# cell.net
KiCad netlist of a schematic drawn in EAGLE
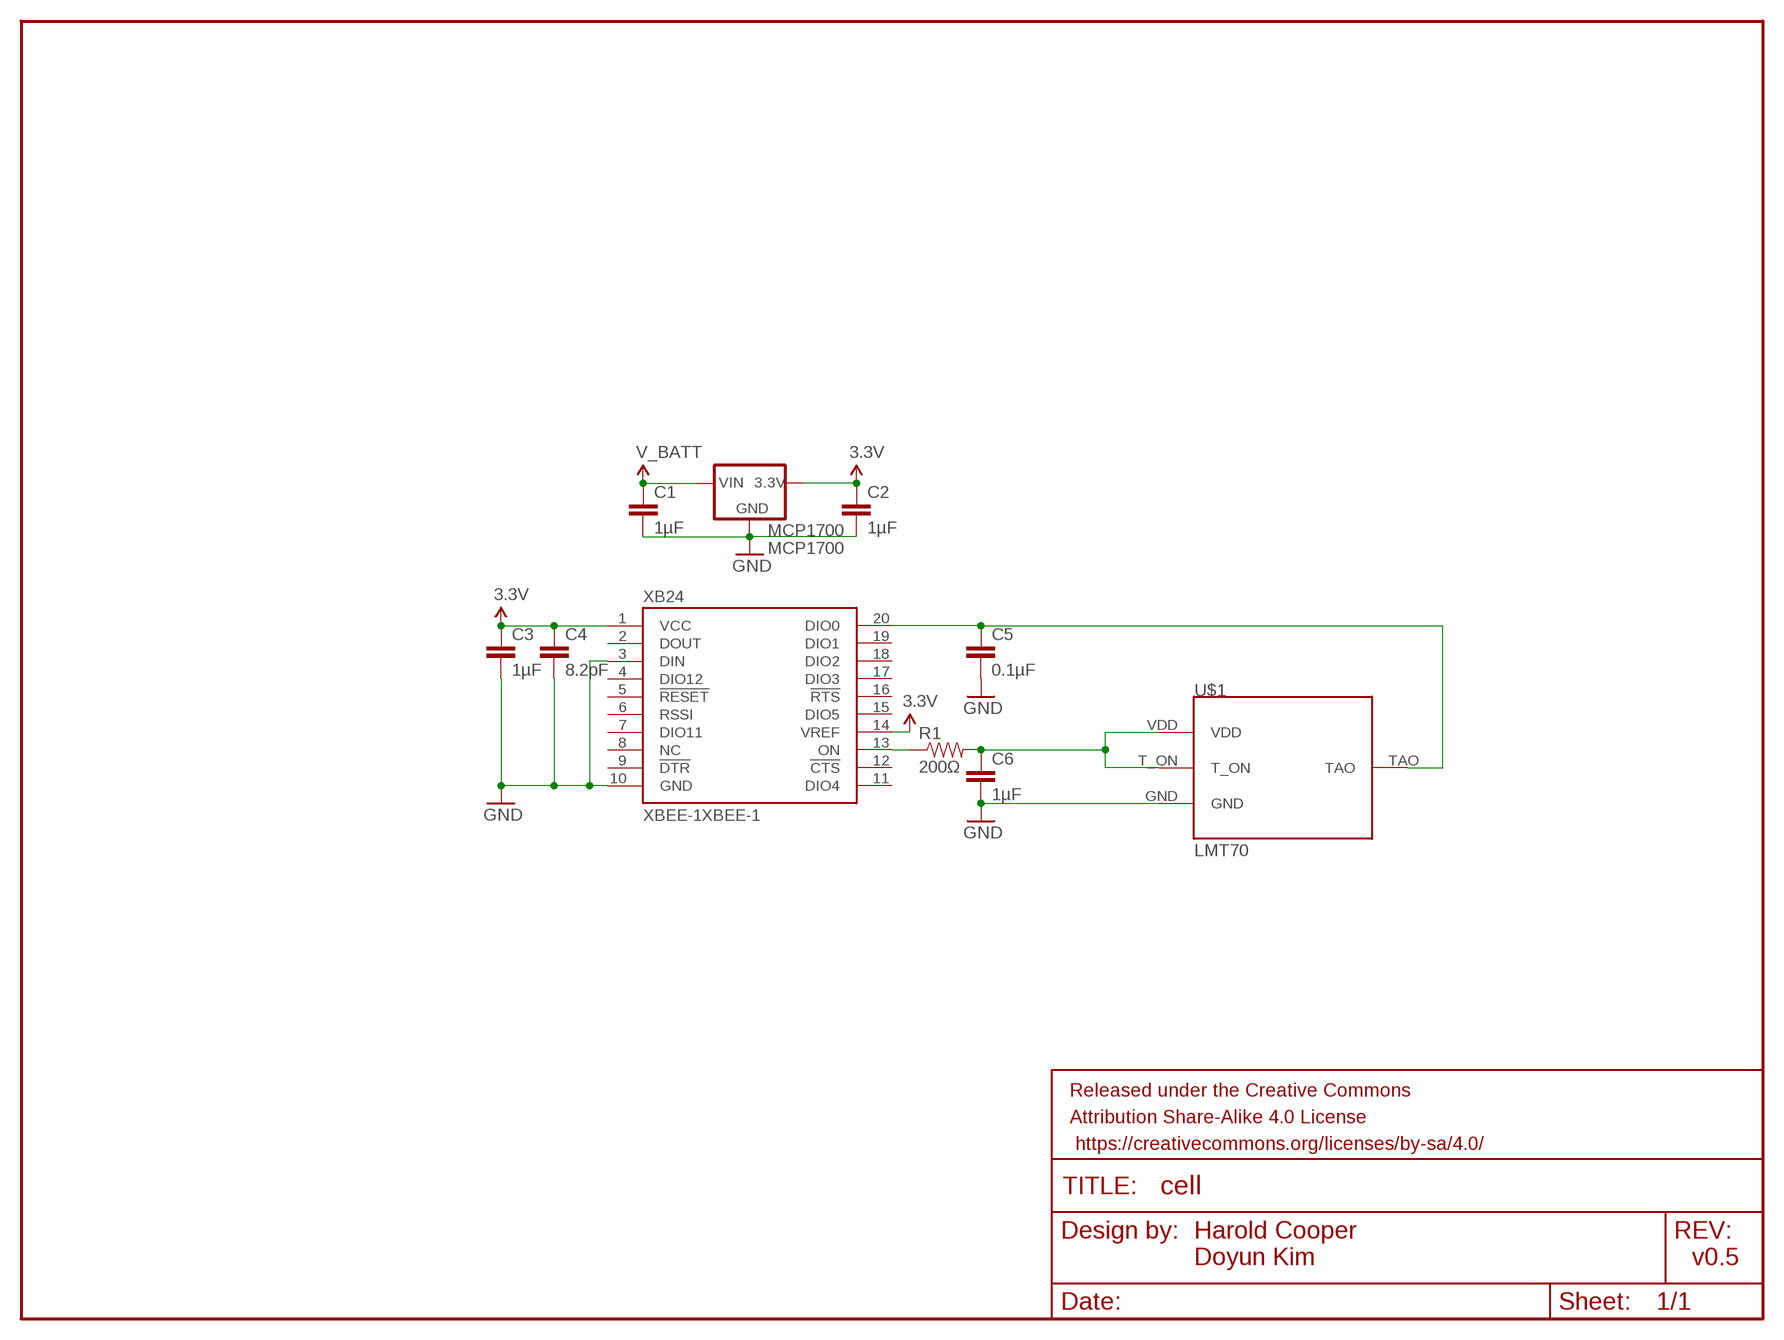
[diagram p0: schematic, sheet 1]

(export (version "E")
  (design (tool "Eeschema 10.0.6"))
  (components
    (comp (ref "C1")
      (value "1µF")
      (footprint "eagle-import:0805")
      (libsource (lib "eagle-import") (part "CAP0805"))
    )
    (comp (ref "C2")
      (value "1µF")
      (footprint "eagle-import:0805")
      (libsource (lib "eagle-import") (part "CAP0805"))
    )
    (comp (ref "C3")
      (value "1µF")
      (footprint "eagle-import:0805")
      (libsource (lib "eagle-import") (part "CAP0805"))
    )
    (comp (ref "C4")
      (value "8.2pF")
      (footprint "eagle-import:0805")
      (libsource (lib "eagle-import") (part "CAP0805"))
    )
    (comp (ref "C5")
      (value "0.1µF")
      (footprint "eagle-import:0805")
      (libsource (lib "eagle-import") (part "CAP0805"))
    )
    (comp (ref "C6")
      (value "1µF")
      (footprint "eagle-import:0805")
      (libsource (lib "eagle-import") (part "CAP0805"))
    )
    (comp (ref "FRAME1")
      (value "FRAME-LETTER")
      (footprint "eagle-import:CREATIVE_COMMONS")
      (libsource (lib "eagle-import") (part "FRAME-LETTER"))
    )
    (comp (ref "MCP1700")
      (value "MCP1700")
      (footprint "eagle-import:SOT-89-3")
      (libsource (lib "eagle-import") (part "MCP1700"))
    )
    (comp (ref "R1")
      (value "200Ω")
      (footprint "eagle-import:0805")
      (libsource (lib "eagle-import") (part "RESISTOR0805-RES"))
    )
    (comp (ref "U$1")
      (value "LMT70")
      (footprint "eagle-import:YFP0004")
      (libsource (lib "eagle-import") (part "LMT70"))
    )
    (comp (ref "XB24")
      (value "XBEE-1XBEE-1")
      (footprint "eagle-import:XBEE-1")
      (libsource (lib "eagle-import") (part "XBEE-1XBEE-1"))
    )
  )
  (nets
    (net (code "1") (name "3.3V") (class "Default")
      (node (ref "C2") (pin "1") (pinfunction "1_1") (pintype "passive"))
      (node (ref "C3") (pin "1") (pinfunction "1_1") (pintype "passive"))
      (node (ref "C4") (pin "1") (pinfunction "1_1") (pintype "passive"))
      (node (ref "MCP1700") (pin "3") (pinfunction "3.3V_3") (pintype "output"))
      (node (ref "XB24") (pin "1") (pinfunction "VCC_1") (pintype "power_in"))
      (node (ref "XB24") (pin "14") (pinfunction "VREF_14") (pintype "power_in"))
    )
    (net (code "2") (name "GND") (class "Default")
      (node (ref "C1") (pin "2") (pinfunction "2_2") (pintype "passive"))
      (node (ref "C2") (pin "2") (pinfunction "2_2") (pintype "passive"))
      (node (ref "C3") (pin "2") (pinfunction "2_2") (pintype "passive"))
      (node (ref "C4") (pin "2") (pinfunction "2_2") (pintype "passive"))
      (node (ref "C5") (pin "2") (pinfunction "2_2") (pintype "passive"))
      (node (ref "C6") (pin "2") (pinfunction "2_2") (pintype "passive"))
      (node (ref "MCP1700") (pin "1") (pinfunction "GND_1") (pintype "power_in"))
      (node (ref "U$1") (pin "GND") (pinfunction "GND_GND") (pintype "input"))
      (node (ref "XB24") (pin "10") (pinfunction "GND_10") (pintype "power_in"))
      (node (ref "XB24") (pin "3") (pinfunction "DIN_3") (pintype "input"))
    )
    (net (code "3") (name "Net-(C6-Pad1)") (class "Default")
      (node (ref "C6") (pin "1") (pinfunction "1_1") (pintype "passive"))
      (node (ref "R1") (pin "2") (pinfunction "2_2") (pintype "passive"))
      (node (ref "U$1") (pin "T_ON") (pinfunction "T_ON_T_ON") (pintype "input"))
      (node (ref "U$1") (pin "VDD") (pinfunction "VDD_VDD") (pintype "input"))
    )
    (net (code "4") (name "Net-(XB24-DIO0)") (class "Default")
      (node (ref "C5") (pin "1") (pinfunction "1_1") (pintype "passive"))
      (node (ref "U$1") (pin "TAO") (pinfunction "TAO_TAO") (pintype "output"))
      (node (ref "XB24") (pin "20") (pinfunction "DIO0_20") (pintype "bidirectional"))
    )
    (net (code "5") (name "Net-(XB24-ON)") (class "Default")
      (node (ref "R1") (pin "1") (pinfunction "1_1") (pintype "passive"))
      (node (ref "XB24") (pin "13") (pinfunction "ON_13") (pintype "bidirectional"))
    )
    (net (code "6") (name "V_BATT") (class "Default")
      (node (ref "C1") (pin "1") (pinfunction "1_1") (pintype "passive"))
      (node (ref "MCP1700") (pin "2") (pinfunction "IN_2") (pintype "power_in"))
    )
    (net (code "7") (name "unconnected-(XB24-DIO1-Pad19)") (class "Default")
      (node (ref "XB24") (pin "19") (pinfunction "DIO1_19") (pintype "bidirectional"))
    )
    (net (code "8") (name "unconnected-(XB24-DIO2-Pad18)") (class "Default")
      (node (ref "XB24") (pin "18") (pinfunction "DIO2_18") (pintype "bidirectional"))
    )
    (net (code "9") (name "unconnected-(XB24-DIO3-Pad17)") (class "Default")
      (node (ref "XB24") (pin "17") (pinfunction "DIO3_17") (pintype "bidirectional"))
    )
    (net (code "10") (name "unconnected-(XB24-DIO4-Pad11)") (class "Default")
      (node (ref "XB24") (pin "11") (pinfunction "DIO4_11") (pintype "bidirectional"))
    )
    (net (code "11") (name "unconnected-(XB24-DIO5-Pad15)") (class "Default")
      (node (ref "XB24") (pin "15") (pinfunction "DIO5_15") (pintype "bidirectional"))
    )
    (net (code "12") (name "unconnected-(XB24-DIO11-Pad7)") (class "Default")
      (node (ref "XB24") (pin "7") (pinfunction "DIO11_7") (pintype "bidirectional"))
    )
    (net (code "13") (name "unconnected-(XB24-DIO12-Pad4)") (class "Default")
      (node (ref "XB24") (pin "4") (pinfunction "DIO12_4") (pintype "bidirectional"))
    )
    (net (code "14") (name "unconnected-(XB24-DOUT-Pad2)") (class "Default")
      (node (ref "XB24") (pin "2") (pinfunction "DOUT_2") (pintype "output"))
    )
    (net (code "15") (name "unconnected-(XB24-NC-Pad8)") (class "Default")
      (node (ref "XB24") (pin "8") (pinfunction "NC_8") (pintype "no_connect"))
    )
    (net (code "16") (name "unconnected-(XB24-RSSI-Pad6)") (class "Default")
      (node (ref "XB24") (pin "6") (pinfunction "RSSI_6") (pintype "bidirectional"))
    )
    (net (code "17") (name "unconnected-(XB24-~{CTS}-Pad12)") (class "Default")
      (node (ref "XB24") (pin "12") (pinfunction "~{CTS}_12") (pintype "output"))
    )
    (net (code "18") (name "unconnected-(XB24-~{DTR}-Pad9)") (class "Default")
      (node (ref "XB24") (pin "9") (pinfunction "~{DTR}_9") (pintype "bidirectional"))
    )
    (net (code "19") (name "unconnected-(XB24-~{RESET}-Pad5)") (class "Default")
      (node (ref "XB24") (pin "5") (pinfunction "~{RESET}_5") (pintype "input"))
    )
    (net (code "20") (name "unconnected-(XB24-~{RTS}-Pad16)") (class "Default")
      (node (ref "XB24") (pin "16") (pinfunction "~{RTS}_16") (pintype "input"))
    )
  )
)
